# MAPLE-CUN-V017-routed.net
KiCad netlist of a schematic drawn in EAGLE
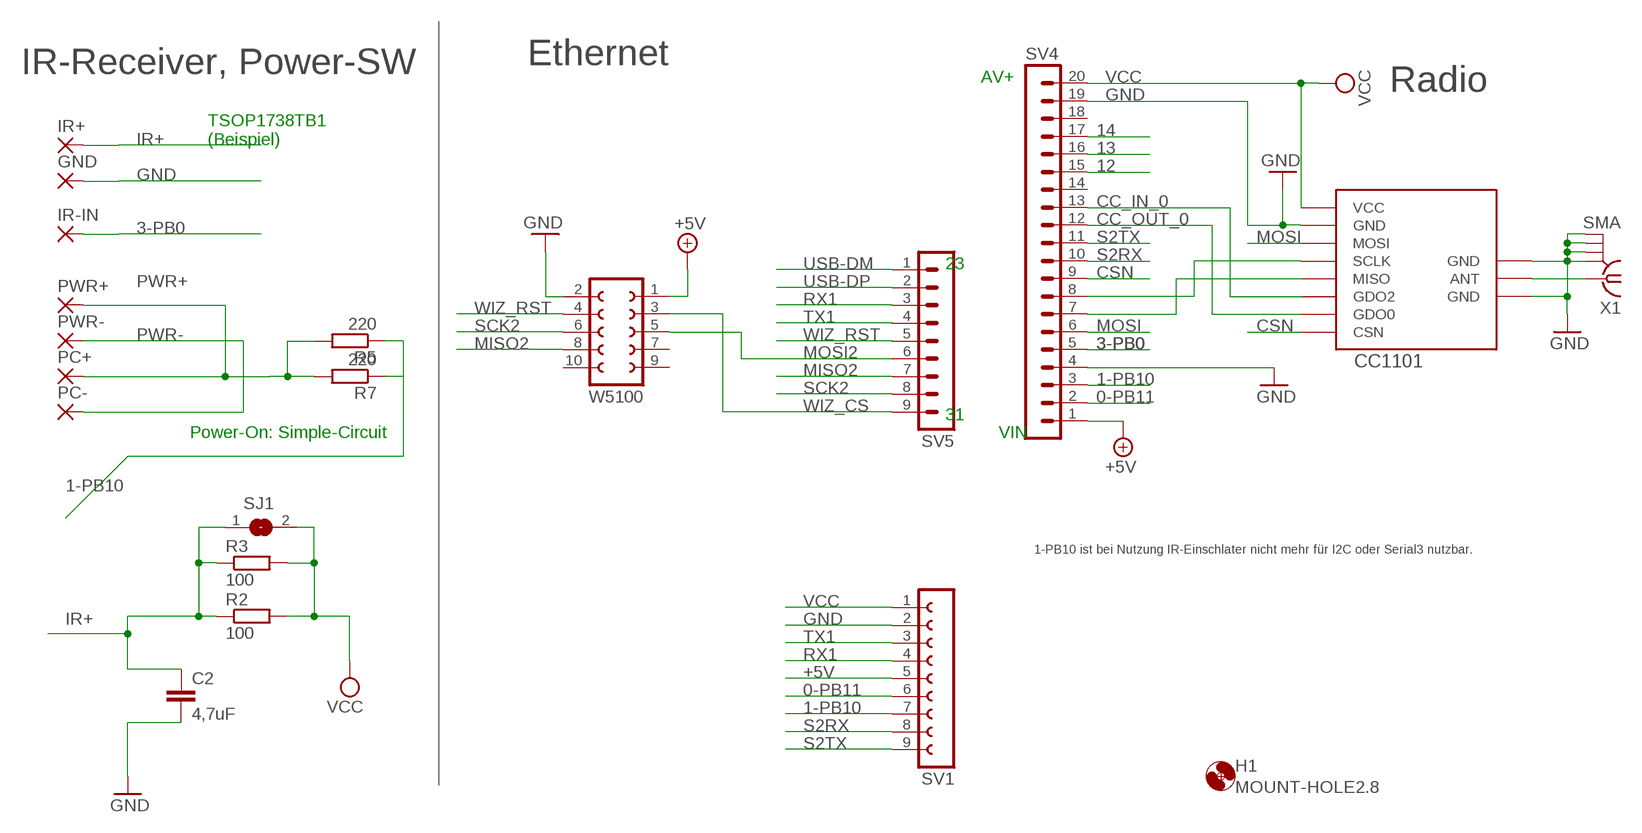
[diagram p0: schematic, sheet 1]

(export (version "E")
  (design (tool "Eeschema 10.0.6"))
  (components
    (comp (ref "C2")
      (value "4,7uF")
      (footprint "eagle-import:C1206K")
      (libsource (lib "eagle-import") (part "C-EUC1206K"))
    )
    (comp (ref "CC1101")
      (value "CC1101_MODULE1SMD")
      (footprint "eagle-import:CC1101_MODULE1_SMD")
      (libsource (lib "eagle-import") (part "CC1101_MODULE1SMD"))
    )
    (comp (ref "GND")
      (value "SMD2")
      (footprint "eagle-import:SMD1,27-2,54")
      (libsource (lib "eagle-import") (part "SMD2"))
    )
    (comp (ref "H1")
      (value "MOUNT-HOLE2.8")
      (footprint "eagle-import:2,8")
      (libsource (lib "eagle-import") (part "MOUNT-HOLE2.8"))
    )
    (comp (ref "IR+")
      (value "SMD2")
      (footprint "eagle-import:SMD1,27-2,54")
      (libsource (lib "eagle-import") (part "SMD2"))
    )
    (comp (ref "IR-IN")
      (value "SMD2")
      (footprint "eagle-import:SMD1,27-2,54")
      (libsource (lib "eagle-import") (part "SMD2"))
    )
    (comp (ref "PC+")
      (value "SMD2")
      (footprint "eagle-import:SMD1,27-2,54")
      (libsource (lib "eagle-import") (part "SMD2"))
    )
    (comp (ref "PC-")
      (value "SMD2")
      (footprint "eagle-import:SMD1,27-2,54")
      (libsource (lib "eagle-import") (part "SMD2"))
    )
    (comp (ref "PWR+")
      (value "SMD2")
      (footprint "eagle-import:SMD1,27-2,54")
      (libsource (lib "eagle-import") (part "SMD2"))
    )
    (comp (ref "PWR-")
      (value "SMD2")
      (footprint "eagle-import:SMD1,27-2,54")
      (libsource (lib "eagle-import") (part "SMD2"))
    )
    (comp (ref "R2")
      (value "100")
      (footprint "eagle-import:0204_7")
      (libsource (lib "eagle-import") (part "R-EU_0204/7"))
    )
    (comp (ref "R3")
      (value "100")
      (footprint "eagle-import:R0805W")
      (libsource (lib "eagle-import") (part "R-EU_R0805W"))
    )
    (comp (ref "R5")
      (value "220")
      (footprint "eagle-import:0204_7")
      (libsource (lib "eagle-import") (part "R-EU_0204/7"))
    )
    (comp (ref "R7")
      (value "220")
      (footprint "eagle-import:R0805W")
      (libsource (lib "eagle-import") (part "R-EU_R0805W"))
    )
    (comp (ref "SJ1") (value "SJ") (footprint "eagle-import:SJ") (libsource (lib "eagle-import") (part "SJ")))
    (comp (ref "SV1")
      (value "FE09-1")
      (footprint "eagle-import:FE09")
      (libsource (lib "eagle-import") (part "FE09-1"))
    )
    (comp (ref "SV4")
      (value "MA20-1")
      (footprint "eagle-import:MA20-1")
      (libsource (lib "eagle-import") (part "MA20-1"))
    )
    (comp (ref "SV5")
      (value "MA09-1")
      (footprint "eagle-import:MA09-1")
      (libsource (lib "eagle-import") (part "MA09-1"))
    )
    (comp (ref "W5100")
      (value "FE05-2")
      (footprint "eagle-import:FE05-2")
      (libsource (lib "eagle-import") (part "FE05-2"))
    )
    (comp (ref "X1")
      (value "SMA")
      (footprint "eagle-import:SMA")
      (libsource (lib "eagle-import") (part "SMA"))
    )
  )
  (nets
    (net (code "1") (name "+5V") (class "Default")
      (node (ref "SV1") (pin "5") (pinfunction "5_5") (pintype "passive"))
      (node (ref "SV4") (pin "1") (pinfunction "1_1") (pintype "passive"))
      (node (ref "W5100") (pin "1") (pinfunction "1_1") (pintype "passive"))
    )
    (net (code "2") (name "/0-PB11") (class "Default")
      (node (ref "SV1") (pin "6") (pinfunction "6_6") (pintype "passive"))
      (node (ref "SV4") (pin "2") (pinfunction "2_2") (pintype "passive"))
    )
    (net (code "3") (name "/1-PB10") (class "Default")
      (node (ref "R5") (pin "1") (pinfunction "1_1") (pintype "passive"))
      (node (ref "R7") (pin "1") (pinfunction "1_1") (pintype "passive"))
      (node (ref "SV1") (pin "7") (pinfunction "7_7") (pintype "passive"))
      (node (ref "SV4") (pin "3") (pinfunction "3_3") (pintype "passive"))
    )
    (net (code "4") (name "/3-PB0") (class "Default")
      (node (ref "IR-IN") (pin "1") (pinfunction "P_1") (pintype "passive"))
      (node (ref "SV4") (pin "5") (pinfunction "5_5") (pintype "passive"))
    )
    (net (code "5") (name "/12") (class "Default")
      (node (ref "SV4") (pin "15") (pinfunction "15_15") (pintype "passive"))
    )
    (net (code "6") (name "/13") (class "Default")
      (node (ref "SV4") (pin "16") (pinfunction "16_16") (pintype "passive"))
    )
    (net (code "7") (name "/14") (class "Default")
      (node (ref "SV4") (pin "17") (pinfunction "17_17") (pintype "passive"))
    )
    (net (code "8") (name "/CC_IN_0") (class "Default")
      (node (ref "CC1101") (pin "GDO2") (pinfunction "GDO2_GDO2") (pintype "bidirectional"))
      (node (ref "SV4") (pin "13") (pinfunction "13_13") (pintype "passive"))
    )
    (net (code "9") (name "/CC_OUT_0") (class "Default")
      (node (ref "CC1101") (pin "GDO0") (pinfunction "GDO0_GDO0") (pintype "bidirectional"))
      (node (ref "SV4") (pin "12") (pinfunction "12_12") (pintype "passive"))
    )
    (net (code "10") (name "/CSN") (class "Default")
      (node (ref "CC1101") (pin "CSN") (pinfunction "CSN_CSN") (pintype "bidirectional"))
      (node (ref "SV4") (pin "9") (pinfunction "9_9") (pintype "passive"))
    )
    (net (code "11") (name "/IR+") (class "Default")
      (node (ref "C2") (pin "1") (pinfunction "1_1") (pintype "passive"))
      (node (ref "IR+") (pin "1") (pinfunction "P_1") (pintype "passive"))
      (node (ref "R2") (pin "1") (pinfunction "1_1") (pintype "passive"))
      (node (ref "R3") (pin "1") (pinfunction "1_1") (pintype "passive"))
      (node (ref "SJ1") (pin "1") (pinfunction "1_1") (pintype "passive"))
    )
    (net (code "12") (name "/MISO2") (class "Default")
      (node (ref "SV5") (pin "7") (pinfunction "7_7") (pintype "passive"))
      (node (ref "W5100") (pin "8") (pinfunction "8_8") (pintype "passive"))
    )
    (net (code "13") (name "/MOSI") (class "Default")
      (node (ref "CC1101") (pin "MOSI") (pinfunction "MOSI_MOSI") (pintype "bidirectional"))
      (node (ref "SV4") (pin "6") (pinfunction "6_6") (pintype "passive"))
    )
    (net (code "14") (name "/MOSI2") (class "Default")
      (node (ref "SV5") (pin "6") (pinfunction "6_6") (pintype "passive"))
      (node (ref "W5100") (pin "5") (pinfunction "5_5") (pintype "passive"))
    )
    (net (code "15") (name "/PWR+") (class "Default")
      (node (ref "PC+") (pin "1") (pinfunction "P_1") (pintype "passive"))
      (node (ref "PWR+") (pin "1") (pinfunction "P_1") (pintype "passive"))
      (node (ref "R5") (pin "2") (pinfunction "2_2") (pintype "passive"))
      (node (ref "R7") (pin "2") (pinfunction "2_2") (pintype "passive"))
    )
    (net (code "16") (name "/PWR-") (class "Default")
      (node (ref "PC-") (pin "1") (pinfunction "P_1") (pintype "passive"))
      (node (ref "PWR-") (pin "1") (pinfunction "P_1") (pintype "passive"))
    )
    (net (code "17") (name "/RX1") (class "Default")
      (node (ref "SV1") (pin "4") (pinfunction "4_4") (pintype "passive"))
      (node (ref "SV5") (pin "3") (pinfunction "3_3") (pintype "passive"))
    )
    (net (code "18") (name "/S2RX") (class "Default")
      (node (ref "SV1") (pin "8") (pinfunction "8_8") (pintype "passive"))
      (node (ref "SV4") (pin "10") (pinfunction "10_10") (pintype "passive"))
    )
    (net (code "19") (name "/S2TX") (class "Default")
      (node (ref "SV1") (pin "9") (pinfunction "9_9") (pintype "passive"))
      (node (ref "SV4") (pin "11") (pinfunction "11_11") (pintype "passive"))
    )
    (net (code "20") (name "/SCK2") (class "Default")
      (node (ref "SV5") (pin "8") (pinfunction "8_8") (pintype "passive"))
      (node (ref "W5100") (pin "6") (pinfunction "6_6") (pintype "passive"))
    )
    (net (code "21") (name "/TX1") (class "Default")
      (node (ref "SV1") (pin "3") (pinfunction "3_3") (pintype "passive"))
      (node (ref "SV5") (pin "4") (pinfunction "4_4") (pintype "passive"))
    )
    (net (code "22") (name "/USB-DM") (class "Default")
      (node (ref "SV5") (pin "1") (pinfunction "1_1") (pintype "passive"))
    )
    (net (code "23") (name "/USB-DP") (class "Default")
      (node (ref "SV5") (pin "2") (pinfunction "2_2") (pintype "passive"))
    )
    (net (code "24") (name "/WIZ_CS") (class "Default")
      (node (ref "SV5") (pin "9") (pinfunction "9_9") (pintype "passive"))
      (node (ref "W5100") (pin "3") (pinfunction "3_3") (pintype "passive"))
    )
    (net (code "25") (name "/WIZ_RST") (class "Default")
      (node (ref "SV5") (pin "5") (pinfunction "5_5") (pintype "passive"))
      (node (ref "W5100") (pin "4") (pinfunction "4_4") (pintype "passive"))
    )
    (net (code "26") (name "GND") (class "Default")
      (node (ref "C2") (pin "2") (pinfunction "2_2") (pintype "passive"))
      (node (ref "CC1101") (pin "GND@0") (pinfunction "GND_GND@0") (pintype "power_in"))
      (node (ref "CC1101") (pin "GND@1") (pinfunction "GND_GND@1") (pintype "power_in"))
      (node (ref "CC1101") (pin "GND@2") (pinfunction "GND_GND@2") (pintype "power_in"))
      (node (ref "GND") (pin "1") (pinfunction "P_1") (pintype "passive"))
      (node (ref "SV1") (pin "2") (pinfunction "2_2") (pintype "passive"))
      (node (ref "SV4") (pin "19") (pinfunction "19_19") (pintype "passive"))
      (node (ref "SV4") (pin "4") (pinfunction "4_4") (pintype "passive"))
      (node (ref "W5100") (pin "2") (pinfunction "2_2") (pintype "passive"))
      (node (ref "X1") (pin "GND@1") (pinfunction "2_GND@1") (pintype "passive"))
      (node (ref "X1") (pin "GND@2") (pinfunction "3_GND@2") (pintype "passive"))
      (node (ref "X1") (pin "GND@3") (pinfunction "4_GND@3") (pintype "passive"))
      (node (ref "X1") (pin "GND@4") (pinfunction "5_GND@4") (pintype "passive"))
    )
    (net (code "27") (name "Net-(CC1101-PadANT)") (class "Default")
      (node (ref "CC1101") (pin "ANT") (pinfunction "ANT_ANT") (pintype "output"))
      (node (ref "X1") (pin "1") (pinfunction "1_1") (pintype "passive"))
    )
    (net (code "28") (name "Net-(CC1101-PadMISO)") (class "Default")
      (node (ref "CC1101") (pin "MISO") (pinfunction "MISO_MISO") (pintype "bidirectional"))
      (node (ref "SV4") (pin "7") (pinfunction "7_7") (pintype "passive"))
    )
    (net (code "29") (name "Net-(CC1101-PadSCLK)") (class "Default")
      (node (ref "CC1101") (pin "SCLK") (pinfunction "SCLK_SCLK") (pintype "bidirectional"))
      (node (ref "SV4") (pin "8") (pinfunction "8_8") (pintype "passive"))
    )
    (net (code "30") (name "VCC") (class "Default")
      (node (ref "CC1101") (pin "VCC") (pinfunction "VCC_VCC") (pintype "power_in"))
      (node (ref "R2") (pin "2") (pinfunction "2_2") (pintype "passive"))
      (node (ref "R3") (pin "2") (pinfunction "2_2") (pintype "passive"))
      (node (ref "SJ1") (pin "2") (pinfunction "2_2") (pintype "passive"))
      (node (ref "SV1") (pin "1") (pinfunction "1_1") (pintype "passive"))
      (node (ref "SV4") (pin "20") (pinfunction "20_20") (pintype "passive"))
    )
    (net (code "31") (name "unconnected-(SV4-Pad14)") (class "Default")
      (node (ref "SV4") (pin "14") (pinfunction "14_14") (pintype "passive"))
    )
    (net (code "32") (name "unconnected-(SV4-Pad18)") (class "Default")
      (node (ref "SV4") (pin "18") (pinfunction "18_18") (pintype "passive"))
    )
    (net (code "33") (name "unconnected-(W5100-Pad7)") (class "Default")
      (node (ref "W5100") (pin "7") (pinfunction "7_7") (pintype "passive"))
    )
    (net (code "34") (name "unconnected-(W5100-Pad9)") (class "Default")
      (node (ref "W5100") (pin "9") (pinfunction "9_9") (pintype "passive"))
    )
    (net (code "35") (name "unconnected-(W5100-Pad10)") (class "Default")
      (node (ref "W5100") (pin "10") (pinfunction "10_10") (pintype "passive"))
    )
  )
)
